# SCH_website_2025-04-25.net
KiCad netlist of a schematic drawn in EasyEDA
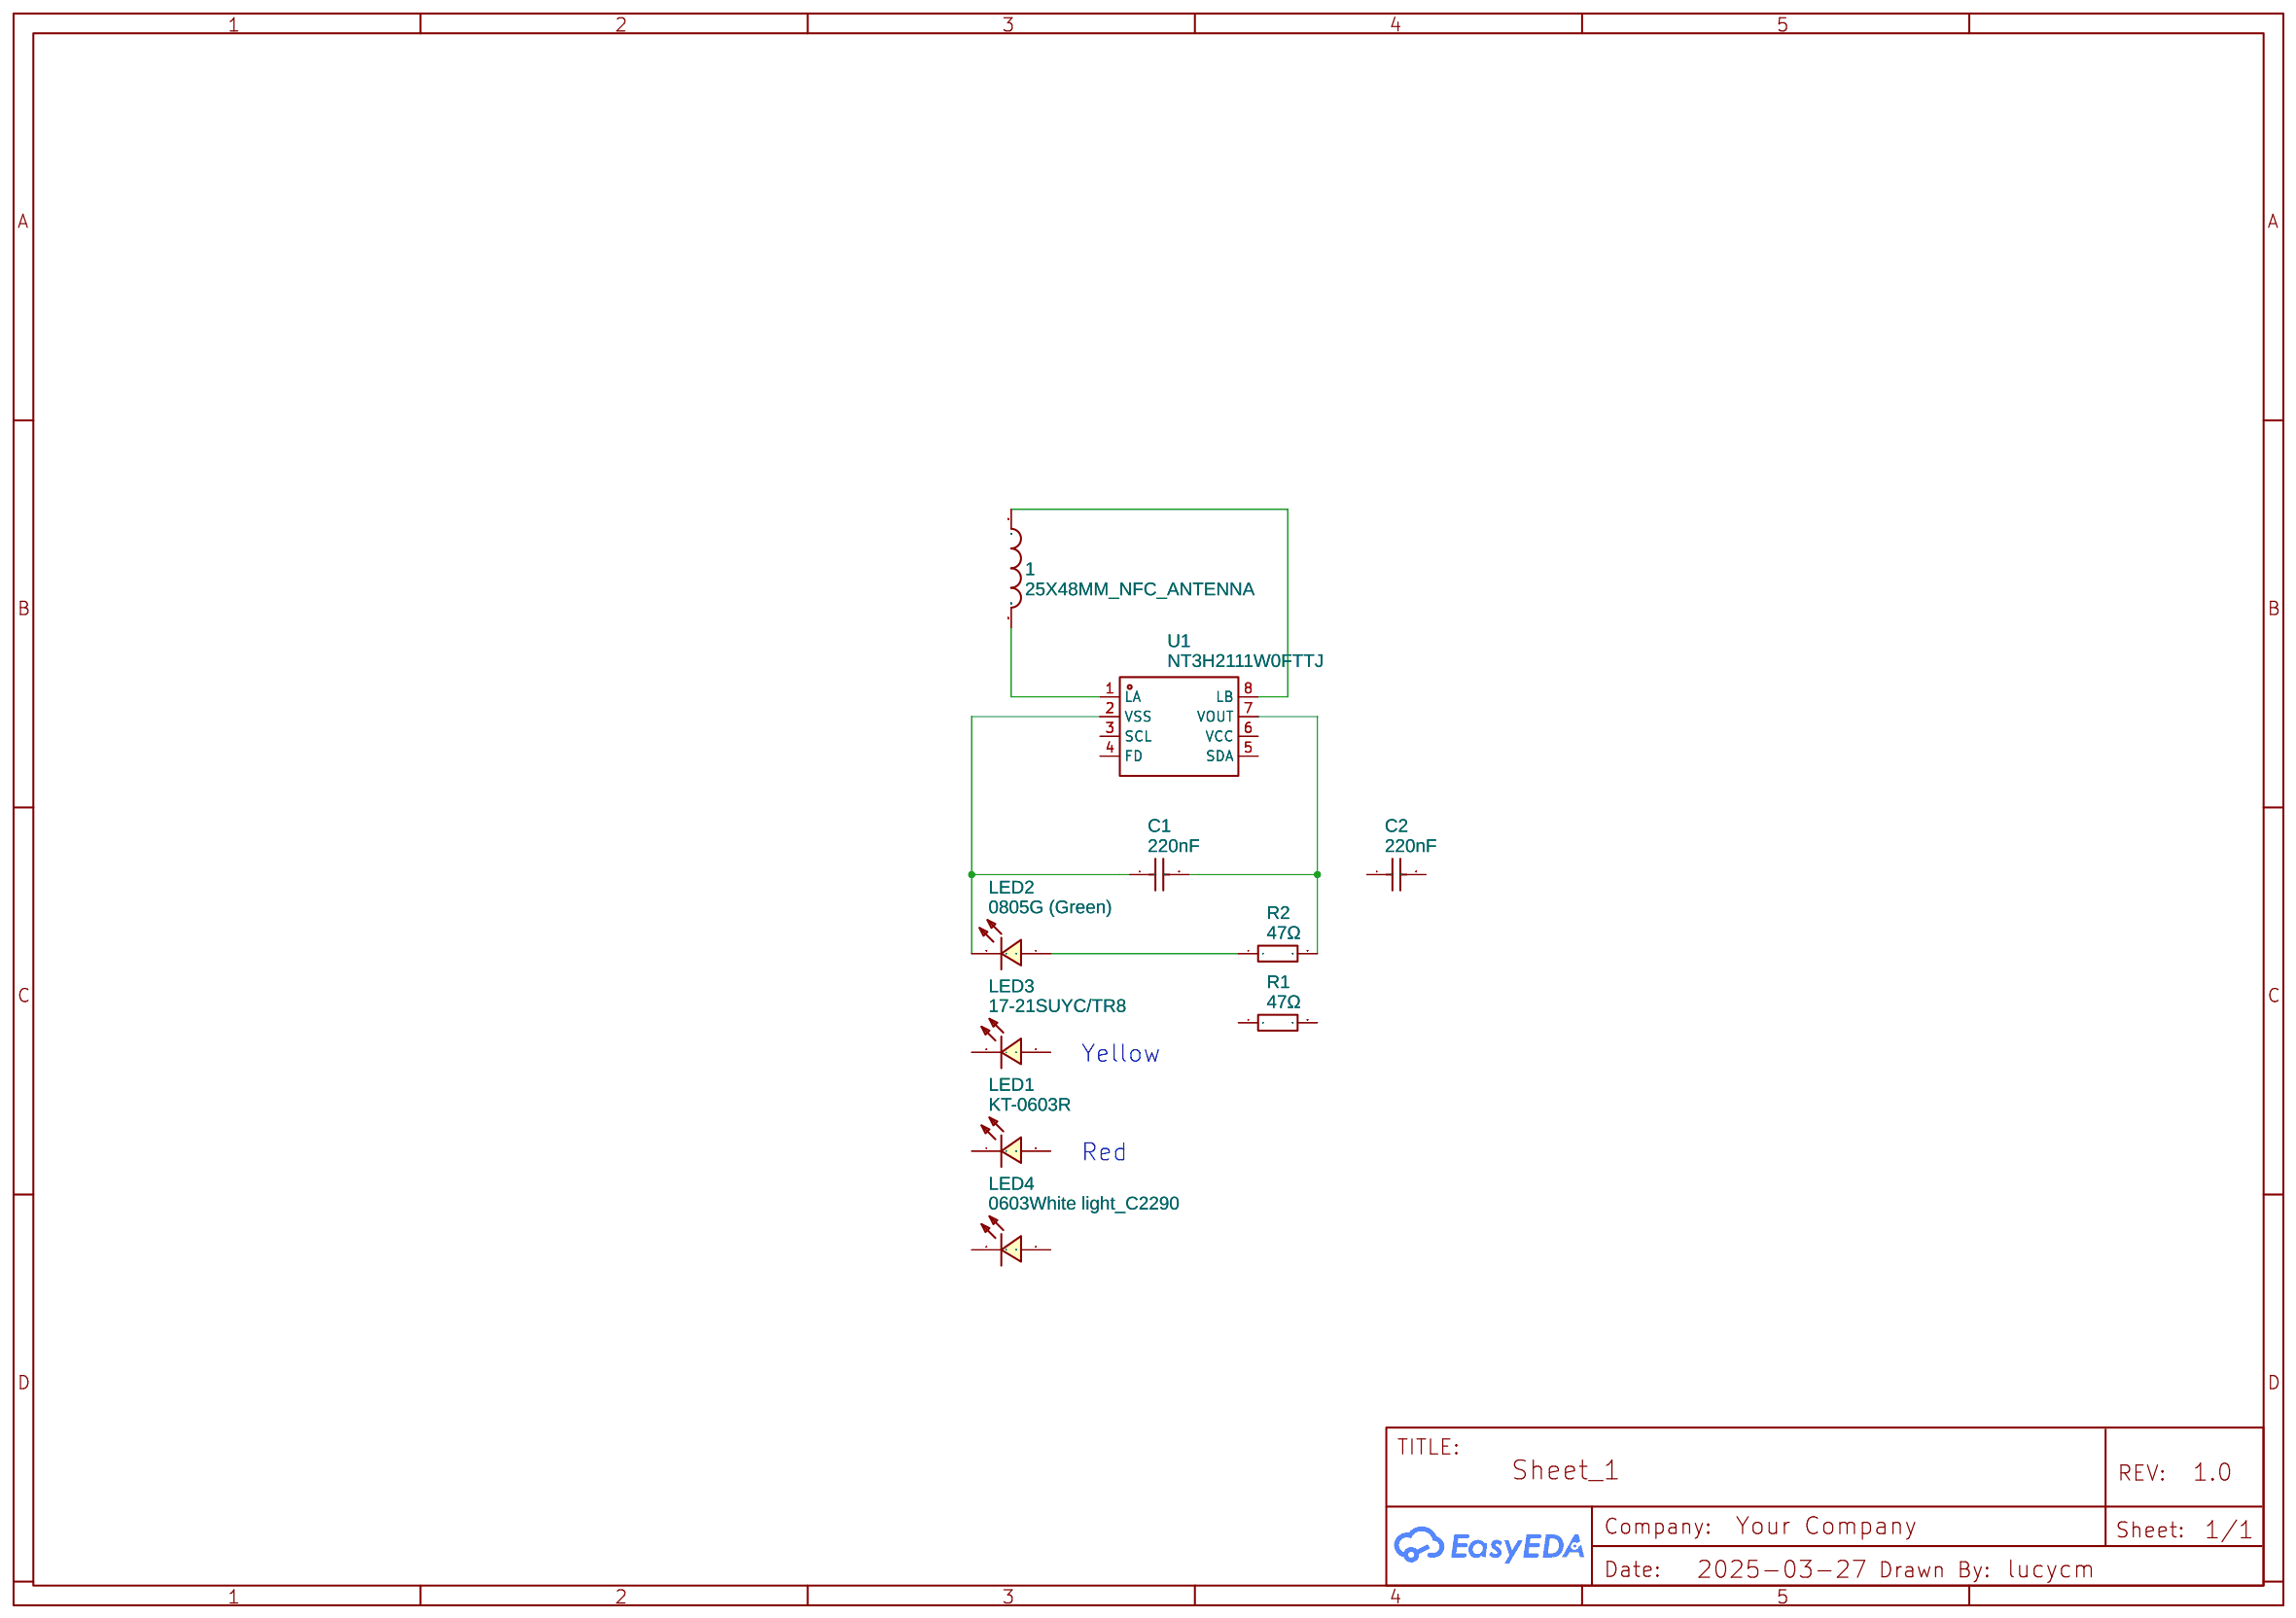
[diagram p0: schematic sheet]

(export (version "E")
  (design (tool "Eeschema 10.0.6"))
  (components
    (comp (ref "1") (value "25X48MM_NFC_ANTENNA") (libsource (lib "") (part "25X48MM_NFC_ANTENNA")))
    (comp (ref "C1")
      (value "220nF")
      (fields
        (field (name "Manufacturer Part") "CL05B224KO5NNNC")
        (field (name "Manufacturer") "SAMSUNG(三星)")
      )
      (libsource (lib "") (part "CL05B224KO5NNNC"))
    )
    (comp (ref "C2")
      (value "220nF")
      (fields
        (field (name "Manufacturer Part") "CL05B224KO5NNNC")
        (field (name "Manufacturer") "SAMSUNG(三星)")
      )
      (libsource (lib "") (part "CL05B224KO5NNNC"))
    )
    (comp (ref "LED1")
      (value "KT-0603R")
      (fields (field (name "Manufacturer") "KENTO"))
      (libsource (lib "") (part "KT-0603R"))
    )
    (comp (ref "LED2")
      (value "0805G (Green)")
      (fields (field (name "Manufacturer Part") "KT-0805G") (field (name "Manufacturer") "KENTO"))
      (libsource (lib "") (part "0805G (Green)"))
    )
    (comp (ref "LED3")
      (value "17-21SUYC/TR8")
      (fields (field (name "Manufacturer Part") "KT-0805黄灯") (field (name "Manufacturer") "KENTO"))
      (libsource (lib "") (part "17-21SUYC/TR8"))
    )
    (comp (ref "LED4")
      (value "0603White light_C2290")
      (fields (field (name "Manufacturer Part") "KT-0603W") (field (name "Manufacturer") "KENTO"))
      (libsource (lib "") (part "0603White light_C2290"))
    )
    (comp (ref "R1")
      (value "47Ω")
      (fields
        (field (name "Manufacturer Part") "0603WAF470JT5E")
        (field (name "Manufacturer") "UNI-ROYAL(厚声)")
      )
      (libsource (lib "") (part "0603WAF470JT5E"))
    )
    (comp (ref "R2")
      (value "47Ω")
      (fields
        (field (name "Manufacturer Part") "0603WAF470JT5E")
        (field (name "Manufacturer") "UNI-ROYAL(厚声)")
      )
      (libsource (lib "") (part "0603WAF470JT5E"))
    )
    (comp (ref "U1")
      (value "NT3H2111W0FTTJ")
      (fields (field (name "Manufacturer") "NXP(恩智浦)"))
      (libsource (lib "") (part "NT3H2111W0FTTJ"))
    )
  )
  (nets
    (net (code "1") (name "Net-(LED2-A)") (class "Default")
      (node (ref "LED2") (pin "1") (pinfunction "A_1") (pintype "unspecified"))
      (node (ref "R2") (pin "1") (pinfunction "1_1") (pintype "input"))
    )
    (net (code "2") (name "Net-(LED2-K)") (class "Default")
      (node (ref "C1") (pin "1") (pinfunction "1_1") (pintype "input"))
      (node (ref "LED2") (pin "2") (pinfunction "K_2") (pintype "unspecified"))
      (node (ref "U1") (pin "2") (pinfunction "VSS_2") (pintype "unspecified"))
    )
    (net (code "3") (name "Net-(U1-LA)") (class "Default")
      (node (ref "1") (pin "P$2") (pinfunction "P$2_P$2") (pintype "bidirectional"))
      (node (ref "U1") (pin "1") (pinfunction "LA_1") (pintype "unspecified"))
    )
    (net (code "4") (name "Net-(U1-LB)") (class "Default")
      (node (ref "1") (pin "P$1") (pinfunction "P$1_P$1") (pintype "bidirectional"))
      (node (ref "U1") (pin "8") (pinfunction "LB_8") (pintype "unspecified"))
    )
    (net (code "5") (name "Net-(U1-VOUT)") (class "Default")
      (node (ref "C1") (pin "2") (pinfunction "2_2") (pintype "input"))
      (node (ref "R2") (pin "2") (pinfunction "2_2") (pintype "input"))
      (node (ref "U1") (pin "7") (pinfunction "VOUT_7") (pintype "unspecified"))
    )
    (net (code "6") (name "unconnected-(C2-Pad1)") (class "Default")
      (node (ref "C2") (pin "1") (pinfunction "1_1") (pintype "input"))
    )
    (net (code "7") (name "unconnected-(C2-Pad2)") (class "Default")
      (node (ref "C2") (pin "2") (pinfunction "2_2") (pintype "input"))
    )
    (net (code "8") (name "unconnected-(LED1-A-Pad2)") (class "Default")
      (node (ref "LED1") (pin "2") (pinfunction "A_2") (pintype "unspecified"))
    )
    (net (code "9") (name "unconnected-(LED1-K-Pad1)") (class "Default")
      (node (ref "LED1") (pin "1") (pinfunction "K_1") (pintype "unspecified"))
    )
    (net (code "10") (name "unconnected-(LED3-+-Pad1)") (class "Default")
      (node (ref "LED3") (pin "1") (pinfunction "+_1") (pintype "unspecified"))
    )
    (net (code "11") (name "unconnected-(LED3---Pad2)") (class "Default")
      (node (ref "LED3") (pin "2") (pinfunction "-_2") (pintype "unspecified"))
    )
    (net (code "12") (name "unconnected-(LED4-A-Pad1)") (class "Default")
      (node (ref "LED4") (pin "1") (pinfunction "A_1") (pintype "unspecified"))
    )
    (net (code "13") (name "unconnected-(LED4-K-Pad2)") (class "Default")
      (node (ref "LED4") (pin "2") (pinfunction "K_2") (pintype "unspecified"))
    )
    (net (code "14") (name "unconnected-(R1-Pad1)") (class "Default")
      (node (ref "R1") (pin "1") (pinfunction "1_1") (pintype "input"))
    )
    (net (code "15") (name "unconnected-(R1-Pad2)") (class "Default")
      (node (ref "R1") (pin "2") (pinfunction "2_2") (pintype "input"))
    )
    (net (code "16") (name "unconnected-(U1-FD-Pad4)") (class "Default")
      (node (ref "U1") (pin "4") (pinfunction "FD_4") (pintype "unspecified"))
    )
    (net (code "17") (name "unconnected-(U1-SCL-Pad3)") (class "Default")
      (node (ref "U1") (pin "3") (pinfunction "SCL_3") (pintype "unspecified"))
    )
    (net (code "18") (name "unconnected-(U1-SDA-Pad5)") (class "Default")
      (node (ref "U1") (pin "5") (pinfunction "SDA_5") (pintype "unspecified"))
    )
    (net (code "19") (name "unconnected-(U1-VCC-Pad6)") (class "Default")
      (node (ref "U1") (pin "6") (pinfunction "VCC_6") (pintype "unspecified"))
    )
  )
)
